# STM32.net
KiCad netlist of a schematic drawn in Altium Designer
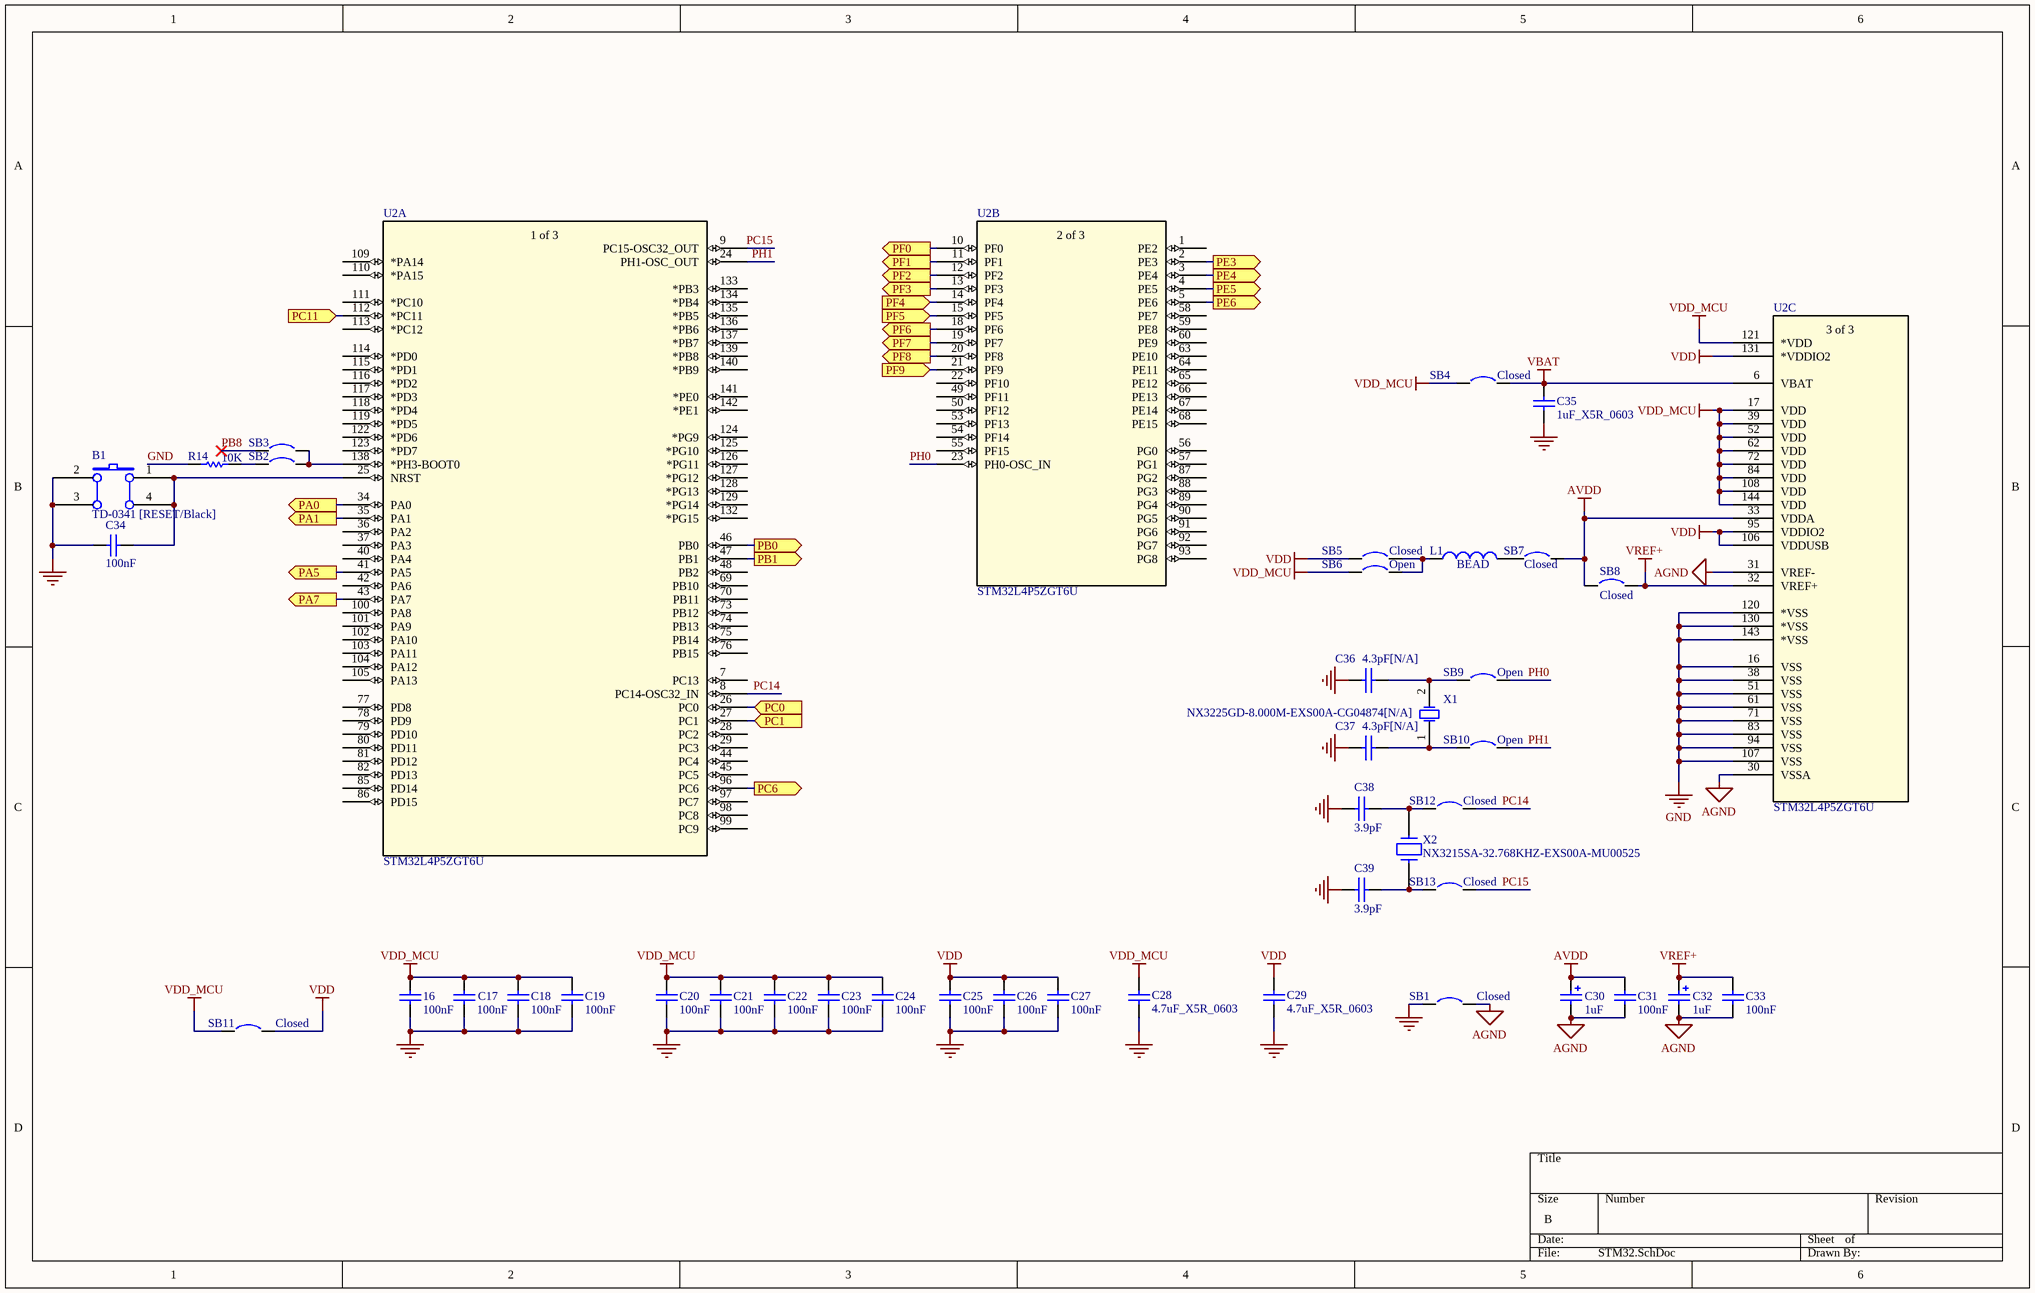
[diagram p0: STM32.SchDoc]

(export (version "E")
  (design (tool "Eeschema 10.0.6"))
  (components
    (comp (ref "16")
      (value "100nF")
      (footprint "0603C")
      (description "Capacitor")
      (fields (field (name "PUBLISHER") "Altium Limited"))
      (libsource (lib "Miscellaneous Devices") (part "Cap"))
    )
    (comp (ref "B1")
      (value "TD-0341 [RESET/Black]")
      (footprint "PB-6X6mm-Black")
      (description "SE PUSHBUTTON")
      (libsource (lib "Documents") (part "SW PUSHBUTTON"))
    )
    (comp (ref "C17")
      (value "100nF")
      (footprint "0603C")
      (description "Capacitor")
      (fields (field (name "PUBLISHER") "Altium Limited"))
      (libsource (lib "Miscellaneous Devices") (part "Cap"))
    )
    (comp (ref "C18")
      (value "100nF")
      (footprint "0603C")
      (description "Capacitor")
      (fields (field (name "PUBLISHER") "Altium Limited"))
      (libsource (lib "Miscellaneous Devices") (part "Cap"))
    )
    (comp (ref "C19")
      (value "100nF")
      (footprint "0603C")
      (description "Capacitor")
      (fields (field (name "PUBLISHER") "Altium Limited"))
      (libsource (lib "Miscellaneous Devices") (part "Cap"))
    )
    (comp (ref "C20")
      (value "100nF")
      (footprint "0603C")
      (description "Capacitor")
      (fields (field (name "PUBLISHER") "Altium Limited"))
      (libsource (lib "Miscellaneous Devices") (part "Cap"))
    )
    (comp (ref "C21")
      (value "100nF")
      (footprint "0603C")
      (description "Capacitor")
      (fields (field (name "PUBLISHER") "Altium Limited"))
      (libsource (lib "Miscellaneous Devices") (part "Cap"))
    )
    (comp (ref "C22")
      (value "100nF")
      (footprint "0603C")
      (description "Capacitor")
      (fields (field (name "PUBLISHER") "Altium Limited"))
      (libsource (lib "Miscellaneous Devices") (part "Cap"))
    )
    (comp (ref "C23")
      (value "100nF")
      (footprint "0603C")
      (description "Capacitor")
      (fields (field (name "PUBLISHER") "Altium Limited"))
      (libsource (lib "Miscellaneous Devices") (part "Cap"))
    )
    (comp (ref "C24")
      (value "100nF")
      (footprint "0603C")
      (description "Capacitor")
      (fields (field (name "PUBLISHER") "Altium Limited"))
      (libsource (lib "Miscellaneous Devices") (part "Cap"))
    )
    (comp (ref "C25")
      (value "100nF")
      (footprint "0603C")
      (description "Capacitor")
      (fields (field (name "PUBLISHER") "Altium Limited"))
      (libsource (lib "Miscellaneous Devices") (part "Cap"))
    )
    (comp (ref "C26")
      (value "100nF")
      (footprint "0603C")
      (description "Capacitor")
      (fields (field (name "PUBLISHER") "Altium Limited"))
      (libsource (lib "Miscellaneous Devices") (part "Cap"))
    )
    (comp (ref "C27")
      (value "100nF")
      (footprint "0603C")
      (description "Capacitor")
      (fields (field (name "PUBLISHER") "Altium Limited"))
      (libsource (lib "Miscellaneous Devices") (part "Cap"))
    )
    (comp (ref "C28")
      (value "4.7uF_X5R_0603")
      (footprint "0603C")
      (description "0603  X5R 4.7uF")
      (fields (field (name "TOLERANCE") "10%"))
      (libsource (lib "MB963_1") (part "CAP SMD 0603  X5R 1µF 25V 10%"))
    )
    (comp (ref "C29")
      (value "4.7uF_X5R_0603")
      (footprint "0603C")
      (description "0603  X5R 4.7uF")
      (fields (field (name "TOLERANCE") "10%"))
      (libsource (lib "MB963_1") (part "CAP SMD 0603  X5R 1µF 25V 10%"))
    )
    (comp (ref "C30")
      (value "1uF")
      (footprint "TAN-A")
      (description "Tan Capacitor,1uF,10%,16V,Tan-A,TAJA105K016R")
      (fields (field (name "Comment") "TAJA105K016R") (field (name "PUBLISHER") "Altium Limited"))
      (libsource (lib "Miscellaneous Devices") (part "Cap Pol1"))
    )
    (comp (ref "C31")
      (value "100nF")
      (footprint "0603C")
      (description "Capacitor")
      (fields (field (name "PUBLISHER") "Altium Limited"))
      (libsource (lib "Miscellaneous Devices") (part "Cap"))
    )
    (comp (ref "C32")
      (value "1uF")
      (footprint "TAN-A")
      (description "Tan Capacitor,1uF,10%,16V,Tan-A,TAJA105K016R")
      (fields (field (name "Comment") "TAJA105K016R") (field (name "PUBLISHER") "Altium Limited"))
      (libsource (lib "Miscellaneous Devices") (part "Cap Pol1"))
    )
    (comp (ref "C33")
      (value "100nF")
      (footprint "0603C")
      (description "Capacitor")
      (fields (field (name "PUBLISHER") "Altium Limited"))
      (libsource (lib "Miscellaneous Devices") (part "Cap"))
    )
    (comp (ref "C34")
      (value "100nF")
      (footprint "0603C")
      (description "Capacitor")
      (fields (field (name "PUBLISHER") "Altium Limited"))
      (libsource (lib "Miscellaneous Devices") (part "CAP"))
    )
    (comp (ref "C35")
      (value "1uF_X5R_0603")
      (footprint "0603C")
      (description "0603  X5R 1µF")
      (fields (field (name "TOLERANCE") "10%"))
      (libsource (lib "MB963_1") (part "CAP SMD 0603  X5R 1µF 25V 10%"))
    )
    (comp (ref "C36")
      (value "4.3pF[N/A]")
      (footprint "0603C")
      (description "Capacitor")
      (libsource (lib "*") (part "CAP"))
    )
    (comp (ref "C37")
      (value "4.3pF[N/A]")
      (footprint "0603C")
      (description "Capacitor")
      (libsource (lib "*") (part "CAP"))
    )
    (comp (ref "C38")
      (value "3.9pF")
      (footprint "0603C")
      (description "Capacitor")
      (libsource (lib "") (part "CAP_1"))
    )
    (comp (ref "C39")
      (value "3.9pF")
      (footprint "0603C")
      (description "Capacitor")
      (libsource (lib "") (part "CAP_1"))
    )
    (comp (ref "L1")
      (value "BEAD")
      (footprint "0603L")
      (description "Inductor")
      (fields (field (name "PUBLISHER") "Altium Limited"))
      (libsource (lib "Miscellaneous Devices") (part "Inductor"))
    )
    (comp (ref "R14")
      (value "10K")
      (footprint "0603R")
      (description "Resistor")
      (fields (field (name "PUBLISHER") "Altium Limited"))
      (libsource (lib "Miscellaneous Devices") (part "res1"))
    )
    (comp (ref "SB1")
      (value "Closed")
      (footprint "SB_0603")
      (description "Circuit Breaker")
      (fields (field (name "PUBLISHER") "Altium Limited"))
      (libsource (lib "MB1167") (part "Circuit Breaker_close"))
    )
    (comp (ref "SB2")
      (value "Circuit Breaker")
      (footprint "SB_0603")
      (fields (field (name "PUBLISHER") "Altium Limited"))
      (libsource (lib "MCD_TOOLS") (part "Circuit Breaker"))
    )
    (comp (ref "SB3")
      (value "Circuit Breaker")
      (footprint "SB_0603")
      (fields (field (name "PUBLISHER") "Altium Limited"))
      (libsource (lib "MCD_TOOLS") (part "Circuit Breaker"))
    )
    (comp (ref "SB4")
      (value "Closed")
      (footprint "SB_0603")
      (description "Circuit Breaker")
      (fields (field (name "PUBLISHER") "Altium Limited"))
      (libsource (lib "MB1167") (part "Circuit Breaker_close"))
    )
    (comp (ref "SB5")
      (value "Closed")
      (footprint "SB_0603")
      (description "Circuit Breaker")
      (fields (field (name "PUBLISHER") "Altium Limited"))
      (libsource (lib "MB1167") (part "Circuit Breaker_close"))
    )
    (comp (ref "SB6")
      (value "Open")
      (footprint "SB_0603")
      (description "Circuit Breaker")
      (fields (field (name "PUBLISHER") "Altium Limited"))
      (libsource (lib "MB1167") (part "Circuit Breaker"))
    )
    (comp (ref "SB7")
      (value "Closed")
      (footprint "SB_0603")
      (description "Circuit Breaker")
      (fields (field (name "PUBLISHER") "Altium Limited"))
      (libsource (lib "MB1167") (part "Circuit Breaker_close"))
    )
    (comp (ref "SB8")
      (value "Closed")
      (footprint "SB_0603")
      (description "Circuit Breaker")
      (fields (field (name "PUBLISHER") "Altium Limited"))
      (libsource (lib "MB1167") (part "Circuit Breaker_close"))
    )
    (comp (ref "SB9")
      (value "Open")
      (footprint "SB_0603")
      (description "Circuit Breaker")
      (fields (field (name "PUBLISHER") "Altium Limited"))
      (libsource (lib "MB1167") (part "Circuit Breaker"))
    )
    (comp (ref "SB10")
      (value "Open")
      (footprint "SB_0603")
      (description "Circuit Breaker")
      (fields (field (name "PUBLISHER") "Altium Limited"))
      (libsource (lib "MB1167") (part "Circuit Breaker"))
    )
    (comp (ref "SB11")
      (value "Closed")
      (footprint "SB_0603")
      (description "Circuit Breaker")
      (fields (field (name "PUBLISHER") "Altium Limited"))
      (libsource (lib "MB1167") (part "Circuit Breaker_close"))
    )
    (comp (ref "SB12")
      (value "Closed")
      (footprint "SB_0603")
      (description "Circuit Breaker")
      (fields (field (name "PUBLISHER") "Altium Limited"))
      (libsource (lib "MB1167") (part "Circuit Breaker"))
    )
    (comp (ref "SB13")
      (value "Closed")
      (footprint "SB_0603")
      (description "Circuit Breaker")
      (fields (field (name "PUBLISHER") "Altium Limited"))
      (libsource (lib "MB1167") (part "Circuit Breaker"))
    )
    (comp (ref "U2")
      (value "STM32L4P5ZGT6U")
      (footprint "LQFP144_STM32_STM")
      (description "No Description Available")
      (fields (field (name "COPYRIGHT") "Copyright (C) 2022 Ultra Librarian. All rights reserved."))
      (libsource (lib "STM32L4P5ZGT6U") (part "STM32L4P5ZGT6U"))
    )
    (comp (ref "X1")
      (value "NX3225GD-8.000M-EXS00A-CG04874[N/A]")
      (footprint "OSC_2SM_3R2x2R5")
      (description "Crystal Oscillator")
      (fields (field (name "PUBLISHER") "Altium Limited"))
      (libsource (lib "MB963_1") (part "XTAL"))
    )
    (comp (ref "X2")
      (value "NX3215SA-32.768KHZ-EXS00A-MU00525")
      (footprint "XTAL_2SM_3R2X1R5")
      (description "Crystal")
      (libsource (lib "MB1167") (part "CRYSTAL_32K"))
    )
  )
  (nets
    (net (code "1") (name "/PA0") (class "Default")
      (node (ref "U2") (pin "34") (pinfunction "PA0_34") (pintype "bidirectional"))
    )
    (net (code "2") (name "/PA1") (class "Default")
      (node (ref "U2") (pin "35") (pinfunction "PA1_35") (pintype "bidirectional"))
    )
    (net (code "3") (name "/PA5") (class "Default")
      (node (ref "U2") (pin "41") (pinfunction "PA5_41") (pintype "bidirectional"))
    )
    (net (code "4") (name "/PA7") (class "Default")
      (node (ref "U2") (pin "43") (pinfunction "PA7_43") (pintype "bidirectional"))
    )
    (net (code "5") (name "/PB0") (class "Default")
      (node (ref "U2") (pin "46") (pinfunction "PB0_46") (pintype "bidirectional"))
    )
    (net (code "6") (name "/PB1") (class "Default")
      (node (ref "U2") (pin "47") (pinfunction "PB1_47") (pintype "bidirectional"))
    )
    (net (code "7") (name "/PB8") (class "Default")
      (node (ref "SB3") (pin "1") (pinfunction "1_1") (pintype "passive+no_connect"))
    )
    (net (code "8") (name "/PC0") (class "Default")
      (node (ref "U2") (pin "26") (pinfunction "PC0_26") (pintype "bidirectional"))
    )
    (net (code "9") (name "/PC1") (class "Default")
      (node (ref "U2") (pin "27") (pinfunction "PC1_27") (pintype "bidirectional"))
    )
    (net (code "10") (name "/PC6") (class "Default")
      (node (ref "U2") (pin "96") (pinfunction "PC6_96") (pintype "bidirectional"))
    )
    (net (code "11") (name "/PC11") (class "Default")
      (node (ref "U2") (pin "112") (pinfunction "*PC11_112") (pintype "bidirectional"))
    )
    (net (code "12") (name "/PC14") (class "Default")
      (node (ref "SB12") (pin "2") (pinfunction "2_2") (pintype "passive"))
      (node (ref "U2") (pin "8") (pinfunction "PC14-OSC32_IN_8") (pintype "bidirectional"))
    )
    (net (code "13") (name "/PC15") (class "Default")
      (node (ref "SB13") (pin "2") (pinfunction "2_2") (pintype "passive"))
      (node (ref "U2") (pin "9") (pinfunction "PC15-OSC32_OUT_9") (pintype "bidirectional"))
    )
    (net (code "14") (name "/PE3") (class "Default")
      (node (ref "U2") (pin "2") (pinfunction "PE3_2") (pintype "bidirectional"))
    )
    (net (code "15") (name "/PE4") (class "Default")
      (node (ref "U2") (pin "3") (pinfunction "PE4_3") (pintype "bidirectional"))
    )
    (net (code "16") (name "/PE5") (class "Default")
      (node (ref "U2") (pin "4") (pinfunction "PE5_4") (pintype "bidirectional"))
    )
    (net (code "17") (name "/PE6") (class "Default")
      (node (ref "U2") (pin "5") (pinfunction "PE6_5") (pintype "bidirectional"))
    )
    (net (code "18") (name "/PF0") (class "Default")
      (node (ref "U2") (pin "10") (pinfunction "PF0_10") (pintype "bidirectional"))
    )
    (net (code "19") (name "/PF1") (class "Default")
      (node (ref "U2") (pin "11") (pinfunction "PF1_11") (pintype "bidirectional"))
    )
    (net (code "20") (name "/PF2") (class "Default")
      (node (ref "U2") (pin "12") (pinfunction "PF2_12") (pintype "bidirectional"))
    )
    (net (code "21") (name "/PF3") (class "Default")
      (node (ref "U2") (pin "13") (pinfunction "PF3_13") (pintype "bidirectional"))
    )
    (net (code "22") (name "/PF4") (class "Default")
      (node (ref "U2") (pin "14") (pinfunction "PF4_14") (pintype "bidirectional"))
    )
    (net (code "23") (name "/PF5") (class "Default")
      (node (ref "U2") (pin "15") (pinfunction "PF5_15") (pintype "bidirectional"))
    )
    (net (code "24") (name "/PF6") (class "Default")
      (node (ref "U2") (pin "18") (pinfunction "PF6_18") (pintype "bidirectional"))
    )
    (net (code "25") (name "/PF7") (class "Default")
      (node (ref "U2") (pin "19") (pinfunction "PF7_19") (pintype "bidirectional"))
    )
    (net (code "26") (name "/PF8") (class "Default")
      (node (ref "U2") (pin "20") (pinfunction "PF8_20") (pintype "bidirectional"))
    )
    (net (code "27") (name "/PF9") (class "Default")
      (node (ref "U2") (pin "21") (pinfunction "PF9_21") (pintype "bidirectional"))
    )
    (net (code "28") (name "/PH0") (class "Default")
      (node (ref "SB9") (pin "2") (pinfunction "2_2") (pintype "passive"))
      (node (ref "U2") (pin "23") (pinfunction "PH0-OSC_IN_23") (pintype "bidirectional"))
    )
    (net (code "29") (name "/PH1") (class "Default")
      (node (ref "SB10") (pin "2") (pinfunction "2_2") (pintype "passive"))
      (node (ref "U2") (pin "24") (pinfunction "PH1-OSC_OUT_24") (pintype "bidirectional"))
    )
    (net (code "30") (name "AGND") (class "Default")
      (node (ref "C30") (pin "2") (pinfunction "2_2") (pintype "passive"))
      (node (ref "C31") (pin "2") (pinfunction "2_2") (pintype "passive"))
      (node (ref "C32") (pin "2") (pinfunction "2_2") (pintype "passive"))
      (node (ref "C33") (pin "2") (pinfunction "2_2") (pintype "passive"))
      (node (ref "SB1") (pin "2") (pinfunction "2_2") (pintype "passive"))
      (node (ref "U2") (pin "30") (pinfunction "VSSA_30") (pintype "passive"))
      (node (ref "U2") (pin "31") (pinfunction "VREF-_31") (pintype "power_in"))
    )
    (net (code "31") (name "AVDD") (class "Default")
      (node (ref "C30") (pin "1") (pinfunction "1_1") (pintype "passive"))
      (node (ref "C31") (pin "1") (pinfunction "1_1") (pintype "passive"))
      (node (ref "SB7") (pin "2") (pinfunction "2_2") (pintype "passive"))
      (node (ref "SB8") (pin "1") (pinfunction "1_1") (pintype "passive"))
      (node (ref "U2") (pin "33") (pinfunction "VDDA_33") (pintype "power_in"))
    )
    (net (code "32") (name "GND") (class "Default")
      (node (ref "16") (pin "2") (pinfunction "2_2") (pintype "passive"))
      (node (ref "B1") (pin "2") (pinfunction "B0_2") (pintype "passive"))
      (node (ref "B1") (pin "3") (pinfunction "B1_3") (pintype "passive"))
      (node (ref "C17") (pin "2") (pinfunction "2_2") (pintype "passive"))
      (node (ref "C18") (pin "2") (pinfunction "2_2") (pintype "passive"))
      (node (ref "C19") (pin "2") (pinfunction "2_2") (pintype "passive"))
      (node (ref "C20") (pin "2") (pinfunction "2_2") (pintype "passive"))
      (node (ref "C21") (pin "2") (pinfunction "2_2") (pintype "passive"))
      (node (ref "C22") (pin "2") (pinfunction "2_2") (pintype "passive"))
      (node (ref "C23") (pin "2") (pinfunction "2_2") (pintype "passive"))
      (node (ref "C24") (pin "2") (pinfunction "2_2") (pintype "passive"))
      (node (ref "C25") (pin "2") (pinfunction "2_2") (pintype "passive"))
      (node (ref "C26") (pin "2") (pinfunction "2_2") (pintype "passive"))
      (node (ref "C27") (pin "2") (pinfunction "2_2") (pintype "passive"))
      (node (ref "C28") (pin "2") (pinfunction "2_2") (pintype "passive"))
      (node (ref "C29") (pin "2") (pinfunction "2_2") (pintype "passive"))
      (node (ref "C34") (pin "2") (pinfunction "2_2") (pintype "passive"))
      (node (ref "C35") (pin "2") (pinfunction "2_2") (pintype "passive"))
      (node (ref "C36") (pin "2") (pinfunction "2_2") (pintype "passive"))
      (node (ref "C37") (pin "2") (pinfunction "2_2") (pintype "passive"))
      (node (ref "C38") (pin "2") (pinfunction "2_2") (pintype "passive"))
      (node (ref "C39") (pin "2") (pinfunction "2_2") (pintype "passive"))
      (node (ref "R14") (pin "2") (pinfunction "2_2") (pintype "passive"))
      (node (ref "SB1") (pin "1") (pinfunction "1_1") (pintype "passive"))
      (node (ref "U2") (pin "107") (pinfunction "VSS_107") (pintype "passive"))
      (node (ref "U2") (pin "120") (pinfunction "*VSS_120") (pintype "passive"))
      (node (ref "U2") (pin "130") (pinfunction "*VSS_130") (pintype "passive"))
      (node (ref "U2") (pin "143") (pinfunction "*VSS_143") (pintype "passive"))
      (node (ref "U2") (pin "16") (pinfunction "VSS_16") (pintype "passive"))
      (node (ref "U2") (pin "38") (pinfunction "VSS_38") (pintype "passive"))
      (node (ref "U2") (pin "51") (pinfunction "VSS_51") (pintype "passive"))
      (node (ref "U2") (pin "61") (pinfunction "VSS_61") (pintype "passive"))
      (node (ref "U2") (pin "71") (pinfunction "VSS_71") (pintype "passive"))
      (node (ref "U2") (pin "83") (pinfunction "VSS_83") (pintype "passive"))
      (node (ref "U2") (pin "94") (pinfunction "VSS_94") (pintype "passive"))
    )
    (net (code "33") (name "Net-(B1-A0)") (class "Default")
      (node (ref "B1") (pin "1") (pinfunction "A0_1") (pintype "passive"))
      (node (ref "B1") (pin "4") (pinfunction "A1_4") (pintype "passive"))
      (node (ref "C34") (pin "1") (pinfunction "1_1") (pintype "passive"))
      (node (ref "U2") (pin "25") (pinfunction "NRST_25") (pintype "bidirectional"))
    )
    (net (code "34") (name "Net-(C38-Pad1)") (class "Default")
      (node (ref "C38") (pin "1") (pinfunction "1_1") (pintype "passive"))
      (node (ref "SB12") (pin "1") (pinfunction "1_1") (pintype "passive"))
      (node (ref "X2") (pin "1") (pinfunction "1_1") (pintype "passive"))
    )
    (net (code "35") (name "Net-(C39-Pad1)") (class "Default")
      (node (ref "C39") (pin "1") (pinfunction "1_1") (pintype "passive"))
      (node (ref "SB13") (pin "1") (pinfunction "1_1") (pintype "passive"))
      (node (ref "X2") (pin "2") (pinfunction "2_2") (pintype "passive"))
    )
    (net (code "36") (name "Net-(L1-Pad1)") (class "Default")
      (node (ref "L1") (pin "1") (pinfunction "1_1") (pintype "passive"))
      (node (ref "SB5") (pin "2") (pinfunction "2_2") (pintype "passive"))
      (node (ref "SB6") (pin "2") (pinfunction "2_2") (pintype "passive"))
    )
    (net (code "37") (name "Net-(L1-Pad2)") (class "Default")
      (node (ref "L1") (pin "2") (pinfunction "2_2") (pintype "passive"))
      (node (ref "SB7") (pin "1") (pinfunction "1_1") (pintype "passive"))
    )
    (net (code "38") (name "Net-(R14-Pad1)") (class "Default")
      (node (ref "R14") (pin "1") (pinfunction "1_1") (pintype "passive"))
      (node (ref "SB2") (pin "1") (pinfunction "1_1") (pintype "passive"))
    )
    (net (code "39") (name "Net-(U2A-*PH3-BOOT0)") (class "Default")
      (node (ref "SB2") (pin "2") (pinfunction "2_2") (pintype "passive"))
      (node (ref "SB3") (pin "2") (pinfunction "2_2") (pintype "passive"))
      (node (ref "U2") (pin "138") (pinfunction "*PH3-BOOT0_138") (pintype "bidirectional"))
    )
    (net (code "40") (name "Net-(X1-OSC1)") (class "Default")
      (node (ref "C37") (pin "1") (pinfunction "1_1") (pintype "passive"))
      (node (ref "SB10") (pin "1") (pinfunction "1_1") (pintype "passive"))
      (node (ref "X1") (pin "1") (pinfunction "OSC1_1") (pintype "passive"))
    )
    (net (code "41") (name "Net-(X1-OSC2)") (class "Default")
      (node (ref "C36") (pin "1") (pinfunction "1_1") (pintype "passive"))
      (node (ref "SB9") (pin "1") (pinfunction "1_1") (pintype "passive"))
      (node (ref "X1") (pin "2") (pinfunction "OSC2_2") (pintype "passive"))
    )
    (net (code "42") (name "VBAT") (class "Default")
      (node (ref "C35") (pin "1") (pinfunction "1_1") (pintype "passive"))
      (node (ref "SB4") (pin "2") (pinfunction "2_2") (pintype "passive"))
      (node (ref "U2") (pin "6") (pinfunction "VBAT_6") (pintype "power_in"))
    )
    (net (code "43") (name "VDD") (class "Default")
      (node (ref "C25") (pin "1") (pinfunction "1_1") (pintype "passive"))
      (node (ref "C26") (pin "1") (pinfunction "1_1") (pintype "passive"))
      (node (ref "C27") (pin "1") (pinfunction "1_1") (pintype "passive"))
      (node (ref "C29") (pin "1") (pinfunction "1_1") (pintype "passive"))
      (node (ref "SB11") (pin "2") (pinfunction "2_2") (pintype "passive"))
      (node (ref "SB5") (pin "1") (pinfunction "1_1") (pintype "passive"))
      (node (ref "U2") (pin "106") (pinfunction "VDDUSB_106") (pintype "power_in"))
      (node (ref "U2") (pin "131") (pinfunction "*VDDIO2_131") (pintype "power_in"))
      (node (ref "U2") (pin "95") (pinfunction "VDDIO2_95") (pintype "power_in"))
    )
    (net (code "44") (name "VDD_MCU") (class "Default")
      (node (ref "16") (pin "1") (pinfunction "1_1") (pintype "passive"))
      (node (ref "C17") (pin "1") (pinfunction "1_1") (pintype "passive"))
      (node (ref "C18") (pin "1") (pinfunction "1_1") (pintype "passive"))
      (node (ref "C19") (pin "1") (pinfunction "1_1") (pintype "passive"))
      (node (ref "C20") (pin "1") (pinfunction "1_1") (pintype "passive"))
      (node (ref "C21") (pin "1") (pinfunction "1_1") (pintype "passive"))
      (node (ref "C22") (pin "1") (pinfunction "1_1") (pintype "passive"))
      (node (ref "C23") (pin "1") (pinfunction "1_1") (pintype "passive"))
      (node (ref "C24") (pin "1") (pinfunction "1_1") (pintype "passive"))
      (node (ref "C28") (pin "1") (pinfunction "1_1") (pintype "passive"))
      (node (ref "SB11") (pin "1") (pinfunction "1_1") (pintype "passive"))
      (node (ref "SB4") (pin "1") (pinfunction "1_1") (pintype "passive"))
      (node (ref "SB6") (pin "1") (pinfunction "1_1") (pintype "passive"))
      (node (ref "U2") (pin "108") (pinfunction "VDD_108") (pintype "power_in"))
      (node (ref "U2") (pin "121") (pinfunction "*VDD_121") (pintype "power_in"))
      (node (ref "U2") (pin "144") (pinfunction "VDD_144") (pintype "power_in"))
      (node (ref "U2") (pin "17") (pinfunction "VDD_17") (pintype "power_in"))
      (node (ref "U2") (pin "39") (pinfunction "VDD_39") (pintype "power_in"))
      (node (ref "U2") (pin "52") (pinfunction "VDD_52") (pintype "power_in"))
      (node (ref "U2") (pin "62") (pinfunction "VDD_62") (pintype "power_in"))
      (node (ref "U2") (pin "72") (pinfunction "VDD_72") (pintype "power_in"))
      (node (ref "U2") (pin "84") (pinfunction "VDD_84") (pintype "power_in"))
    )
    (net (code "45") (name "VREF+") (class "Default")
      (node (ref "C32") (pin "1") (pinfunction "1_1") (pintype "passive"))
      (node (ref "C33") (pin "1") (pinfunction "1_1") (pintype "passive"))
      (node (ref "SB8") (pin "2") (pinfunction "2_2") (pintype "passive"))
      (node (ref "U2") (pin "32") (pinfunction "VREF+_32") (pintype "power_in"))
    )
    (net (code "46") (name "unconnected-(U2A-*PA14-Pad109)") (class "Default")
      (node (ref "U2") (pin "109") (pinfunction "*PA14_109") (pintype "bidirectional"))
    )
    (net (code "47") (name "unconnected-(U2A-*PA15-Pad110)") (class "Default")
      (node (ref "U2") (pin "110") (pinfunction "*PA15_110") (pintype "bidirectional"))
    )
    (net (code "48") (name "unconnected-(U2A-*PB3-Pad133)") (class "Default")
      (node (ref "U2") (pin "133") (pinfunction "*PB3_133") (pintype "bidirectional"))
    )
    (net (code "49") (name "unconnected-(U2A-*PB4-Pad134)") (class "Default")
      (node (ref "U2") (pin "134") (pinfunction "*PB4_134") (pintype "bidirectional"))
    )
    (net (code "50") (name "unconnected-(U2A-*PB5-Pad135)") (class "Default")
      (node (ref "U2") (pin "135") (pinfunction "*PB5_135") (pintype "bidirectional"))
    )
    (net (code "51") (name "unconnected-(U2A-*PB6-Pad136)") (class "Default")
      (node (ref "U2") (pin "136") (pinfunction "*PB6_136") (pintype "bidirectional"))
    )
    (net (code "52") (name "unconnected-(U2A-*PB7-Pad137)") (class "Default")
      (node (ref "U2") (pin "137") (pinfunction "*PB7_137") (pintype "bidirectional"))
    )
    (net (code "53") (name "unconnected-(U2A-*PB8-Pad139)") (class "Default")
      (node (ref "U2") (pin "139") (pinfunction "*PB8_139") (pintype "bidirectional"))
    )
    (net (code "54") (name "unconnected-(U2A-*PB9-Pad140)") (class "Default")
      (node (ref "U2") (pin "140") (pinfunction "*PB9_140") (pintype "bidirectional"))
    )
    (net (code "55") (name "unconnected-(U2A-*PC10-Pad111)") (class "Default")
      (node (ref "U2") (pin "111") (pinfunction "*PC10_111") (pintype "bidirectional"))
    )
    (net (code "56") (name "unconnected-(U2A-*PC12-Pad113)") (class "Default")
      (node (ref "U2") (pin "113") (pinfunction "*PC12_113") (pintype "bidirectional"))
    )
    (net (code "57") (name "unconnected-(U2A-*PD0-Pad114)") (class "Default")
      (node (ref "U2") (pin "114") (pinfunction "*PD0_114") (pintype "bidirectional"))
    )
    (net (code "58") (name "unconnected-(U2A-*PD1-Pad115)") (class "Default")
      (node (ref "U2") (pin "115") (pinfunction "*PD1_115") (pintype "bidirectional"))
    )
    (net (code "59") (name "unconnected-(U2A-*PD2-Pad116)") (class "Default")
      (node (ref "U2") (pin "116") (pinfunction "*PD2_116") (pintype "bidirectional"))
    )
    (net (code "60") (name "unconnected-(U2A-*PD3-Pad117)") (class "Default")
      (node (ref "U2") (pin "117") (pinfunction "*PD3_117") (pintype "bidirectional"))
    )
    (net (code "61") (name "unconnected-(U2A-*PD4-Pad118)") (class "Default")
      (node (ref "U2") (pin "118") (pinfunction "*PD4_118") (pintype "bidirectional"))
    )
    (net (code "62") (name "unconnected-(U2A-*PD5-Pad119)") (class "Default")
      (node (ref "U2") (pin "119") (pinfunction "*PD5_119") (pintype "bidirectional"))
    )
    (net (code "63") (name "unconnected-(U2A-*PD6-Pad122)") (class "Default")
      (node (ref "U2") (pin "122") (pinfunction "*PD6_122") (pintype "bidirectional"))
    )
    (net (code "64") (name "unconnected-(U2A-*PD7-Pad123)") (class "Default")
      (node (ref "U2") (pin "123") (pinfunction "*PD7_123") (pintype "bidirectional"))
    )
    (net (code "65") (name "unconnected-(U2A-*PE0-Pad141)") (class "Default")
      (node (ref "U2") (pin "141") (pinfunction "*PE0_141") (pintype "bidirectional"))
    )
    (net (code "66") (name "unconnected-(U2A-*PE1-Pad142)") (class "Default")
      (node (ref "U2") (pin "142") (pinfunction "*PE1_142") (pintype "bidirectional"))
    )
    (net (code "67") (name "unconnected-(U2A-*PG9-Pad124)") (class "Default")
      (node (ref "U2") (pin "124") (pinfunction "*PG9_124") (pintype "bidirectional"))
    )
    (net (code "68") (name "unconnected-(U2A-*PG10-Pad125)") (class "Default")
      (node (ref "U2") (pin "125") (pinfunction "*PG10_125") (pintype "bidirectional"))
    )
    (net (code "69") (name "unconnected-(U2A-*PG11-Pad126)") (class "Default")
      (node (ref "U2") (pin "126") (pinfunction "*PG11_126") (pintype "bidirectional"))
    )
    (net (code "70") (name "unconnected-(U2A-*PG12-Pad127)") (class "Default")
      (node (ref "U2") (pin "127") (pinfunction "*PG12_127") (pintype "bidirectional"))
    )
    (net (code "71") (name "unconnected-(U2A-*PG13-Pad128)") (class "Default")
      (node (ref "U2") (pin "128") (pinfunction "*PG13_128") (pintype "bidirectional"))
    )
    (net (code "72") (name "unconnected-(U2A-*PG14-Pad129)") (class "Default")
      (node (ref "U2") (pin "129") (pinfunction "*PG14_129") (pintype "bidirectional"))
    )
    (net (code "73") (name "unconnected-(U2A-*PG15-Pad132)") (class "Default")
      (node (ref "U2") (pin "132") (pinfunction "*PG15_132") (pintype "bidirectional"))
    )
    (net (code "74") (name "unconnected-(U2A-PA2-Pad36)") (class "Default")
      (node (ref "U2") (pin "36") (pinfunction "PA2_36") (pintype "bidirectional"))
    )
    (net (code "75") (name "unconnected-(U2A-PA3-Pad37)") (class "Default")
      (node (ref "U2") (pin "37") (pinfunction "PA3_37") (pintype "bidirectional"))
    )
    (net (code "76") (name "unconnected-(U2A-PA4-Pad40)") (class "Default")
      (node (ref "U2") (pin "40") (pinfunction "PA4_40") (pintype "bidirectional"))
    )
    (net (code "77") (name "unconnected-(U2A-PA6-Pad42)") (class "Default")
      (node (ref "U2") (pin "42") (pinfunction "PA6_42") (pintype "bidirectional"))
    )
    (net (code "78") (name "unconnected-(U2A-PA8-Pad100)") (class "Default")
      (node (ref "U2") (pin "100") (pinfunction "PA8_100") (pintype "bidirectional"))
    )
    (net (code "79") (name "unconnected-(U2A-PA9-Pad101)") (class "Default")
      (node (ref "U2") (pin "101") (pinfunction "PA9_101") (pintype "bidirectional"))
    )
    (net (code "80") (name "unconnected-(U2A-PA10-Pad102)") (class "Default")
      (node (ref "U2") (pin "102") (pinfunction "PA10_102") (pintype "bidirectional"))
    )
    (net (code "81") (name "unconnected-(U2A-PA11-Pad103)") (class "Default")
      (node (ref "U2") (pin "103") (pinfunction "PA11_103") (pintype "bidirectional"))
    )
    (net (code "82") (name "unconnected-(U2A-PA12-Pad104)") (class "Default")
      (node (ref "U2") (pin "104") (pinfunction "PA12_104") (pintype "bidirectional"))
    )
    (net (code "83") (name "unconnected-(U2A-PA13-Pad105)") (class "Default")
      (node (ref "U2") (pin "105") (pinfunction "PA13_105") (pintype "bidirectional"))
    )
    (net (code "84") (name "unconnected-(U2A-PB2-Pad48)") (class "Default")
      (node (ref "U2") (pin "48") (pinfunction "PB2_48") (pintype "bidirectional"))
    )
    (net (code "85") (name "unconnected-(U2A-PB10-Pad69)") (class "Default")
      (node (ref "U2") (pin "69") (pinfunction "PB10_69") (pintype "bidirectional"))
    )
    (net (code "86") (name "unconnected-(U2A-PB11-Pad70)") (class "Default")
      (node (ref "U2") (pin "70") (pinfunction "PB11_70") (pintype "bidirectional"))
    )
    (net (code "87") (name "unconnected-(U2A-PB12-Pad73)") (class "Default")
      (node (ref "U2") (pin "73") (pinfunction "PB12_73") (pintype "bidirectional"))
    )
    (net (code "88") (name "unconnected-(U2A-PB13-Pad74)") (class "Default")
      (node (ref "U2") (pin "74") (pinfunction "PB13_74") (pintype "bidirectional"))
    )
    (net (code "89") (name "unconnected-(U2A-PB14-Pad75)") (class "Default")
      (node (ref "U2") (pin "75") (pinfunction "PB14_75") (pintype "bidirectional"))
    )
    (net (code "90") (name "unconnected-(U2A-PB15-Pad76)") (class "Default")
      (node (ref "U2") (pin "76") (pinfunction "PB15_76") (pintype "bidirectional"))
    )
    (net (code "91") (name "unconnected-(U2A-PC2-Pad28)") (class "Default")
      (node (ref "U2") (pin "28") (pinfunction "PC2_28") (pintype "bidirectional"))
    )
    (net (code "92") (name "unconnected-(U2A-PC3-Pad29)") (class "Default")
      (node (ref "U2") (pin "29") (pinfunction "PC3_29") (pintype "bidirectional"))
    )
    (net (code "93") (name "unconnected-(U2A-PC4-Pad44)") (class "Default")
      (node (ref "U2") (pin "44") (pinfunction "PC4_44") (pintype "bidirectional"))
    )
    (net (code "94") (name "unconnected-(U2A-PC5-Pad45)") (class "Default")
      (node (ref "U2") (pin "45") (pinfunction "PC5_45") (pintype "bidirectional"))
    )
    (net (code "95") (name "unconnected-(U2A-PC7-Pad97)") (class "Default")
      (node (ref "U2") (pin "97") (pinfunction "PC7_97") (pintype "bidirectional"))
    )
    (net (code "96") (name "unconnected-(U2A-PC8-Pad98)") (class "Default")
      (node (ref "U2") (pin "98") (pinfunction "PC8_98") (pintype "bidirectional"))
    )
    (net (code "97") (name "unconnected-(U2A-PC9-Pad99)") (class "Default")
      (node (ref "U2") (pin "99") (pinfunction "PC9_99") (pintype "bidirectional"))
    )
    (net (code "98") (name "unconnected-(U2A-PC13-Pad7)") (class "Default")
      (node (ref "U2") (pin "7") (pinfunction "PC13_7") (pintype "bidirectional"))
    )
    (net (code "99") (name "unconnected-(U2A-PD8-Pad77)") (class "Default")
      (node (ref "U2") (pin "77") (pinfunction "PD8_77") (pintype "bidirectional"))
    )
    (net (code "100") (name "unconnected-(U2A-PD9-Pad78)") (class "Default")
      (node (ref "U2") (pin "78") (pinfunction "PD9_78") (pintype "bidirectional"))
    )
    (net (code "101") (name "unconnected-(U2A-PD10-Pad79)") (class "Default")
      (node (ref "U2") (pin "79") (pinfunction "PD10_79") (pintype "bidirectional"))
    )
    (net (code "102") (name "unconnected-(U2A-PD11-Pad80)") (class "Default")
      (node (ref "U2") (pin "80") (pinfunction "PD11_80") (pintype "bidirectional"))
    )
    (net (code "103") (name "unconnected-(U2A-PD12-Pad81)") (class "Default")
      (node (ref "U2") (pin "81") (pinfunction "PD12_81") (pintype "bidirectional"))
    )
    (net (code "104") (name "unconnected-(U2A-PD13-Pad82)") (class "Default")
      (node (ref "U2") (pin "82") (pinfunction "PD13_82") (pintype "bidirectional"))
    )
    (net (code "105") (name "unconnected-(U2A-PD14-Pad85)") (class "Default")
      (node (ref "U2") (pin "85") (pinfunction "PD14_85") (pintype "bidirectional"))
    )
    (net (code "106") (name "unconnected-(U2A-PD15-Pad86)") (class "Default")
      (node (ref "U2") (pin "86") (pinfunction "PD15_86") (pintype "bidirectional"))
    )
    (net (code "107") (name "unconnected-(U2B-PE2-Pad1)") (class "Default")
      (node (ref "U2") (pin "1") (pinfunction "PE2_1") (pintype "bidirectional"))
    )
    (net (code "108") (name "unconnected-(U2B-PE7-Pad58)") (class "Default")
      (node (ref "U2") (pin "58") (pinfunction "PE7_58") (pintype "bidirectional"))
    )
    (net (code "109") (name "unconnected-(U2B-PE8-Pad59)") (class "Default")
      (node (ref "U2") (pin "59") (pinfunction "PE8_59") (pintype "bidirectional"))
    )
    (net (code "110") (name "unconnected-(U2B-PE9-Pad60)") (class "Default")
      (node (ref "U2") (pin "60") (pinfunction "PE9_60") (pintype "bidirectional"))
    )
    (net (code "111") (name "unconnected-(U2B-PE10-Pad63)") (class "Default")
      (node (ref "U2") (pin "63") (pinfunction "PE10_63") (pintype "bidirectional"))
    )
    (net (code "112") (name "unconnected-(U2B-PE11-Pad64)") (class "Default")
      (node (ref "U2") (pin "64") (pinfunction "PE11_64") (pintype "bidirectional"))
    )
    (net (code "113") (name "unconnected-(U2B-PE12-Pad65)") (class "Default")
      (node (ref "U2") (pin "65") (pinfunction "PE12_65") (pintype "bidirectional"))
    )
    (net (code "114") (name "unconnected-(U2B-PE13-Pad66)") (class "Default")
      (node (ref "U2") (pin "66") (pinfunction "PE13_66") (pintype "bidirectional"))
    )
    (net (code "115") (name "unconnected-(U2B-PE14-Pad67)") (class "Default")
      (node (ref "U2") (pin "67") (pinfunction "PE14_67") (pintype "bidirectional"))
    )
    (net (code "116") (name "unconnected-(U2B-PE15-Pad68)") (class "Default")
      (node (ref "U2") (pin "68") (pinfunction "PE15_68") (pintype "bidirectional"))
    )
    (net (code "117") (name "unconnected-(U2B-PF10-Pad22)") (class "Default")
      (node (ref "U2") (pin "22") (pinfunction "PF10_22") (pintype "bidirectional"))
    )
    (net (code "118") (name "unconnected-(U2B-PF11-Pad49)") (class "Default")
      (node (ref "U2") (pin "49") (pinfunction "PF11_49") (pintype "bidirectional"))
    )
    (net (code "119") (name "unconnected-(U2B-PF12-Pad50)") (class "Default")
      (node (ref "U2") (pin "50") (pinfunction "PF12_50") (pintype "bidirectional"))
    )
    (net (code "120") (name "unconnected-(U2B-PF13-Pad53)") (class "Default")
      (node (ref "U2") (pin "53") (pinfunction "PF13_53") (pintype "bidirectional"))
    )
    (net (code "121") (name "unconnected-(U2B-PF14-Pad54)") (class "Default")
      (node (ref "U2") (pin "54") (pinfunction "PF14_54") (pintype "bidirectional"))
    )
    (net (code "122") (name "unconnected-(U2B-PF15-Pad55)") (class "Default")
      (node (ref "U2") (pin "55") (pinfunction "PF15_55") (pintype "bidirectional"))
    )
    (net (code "123") (name "unconnected-(U2B-PG0-Pad56)") (class "Default")
      (node (ref "U2") (pin "56") (pinfunction "PG0_56") (pintype "bidirectional"))
    )
    (net (code "124") (name "unconnected-(U2B-PG1-Pad57)") (class "Default")
      (node (ref "U2") (pin "57") (pinfunction "PG1_57") (pintype "bidirectional"))
    )
    (net (code "125") (name "unconnected-(U2B-PG2-Pad87)") (class "Default")
      (node (ref "U2") (pin "87") (pinfunction "PG2_87") (pintype "bidirectional"))
    )
    (net (code "126") (name "unconnected-(U2B-PG3-Pad88)") (class "Default")
      (node (ref "U2") (pin "88") (pinfunction "PG3_88") (pintype "bidirectional"))
    )
    (net (code "127") (name "unconnected-(U2B-PG4-Pad89)") (class "Default")
      (node (ref "U2") (pin "89") (pinfunction "PG4_89") (pintype "bidirectional"))
    )
    (net (code "128") (name "unconnected-(U2B-PG5-Pad90)") (class "Default")
      (node (ref "U2") (pin "90") (pinfunction "PG5_90") (pintype "bidirectional"))
    )
    (net (code "129") (name "unconnected-(U2B-PG6-Pad91)") (class "Default")
      (node (ref "U2") (pin "91") (pinfunction "PG6_91") (pintype "bidirectional"))
    )
    (net (code "130") (name "unconnected-(U2B-PG7-Pad92)") (class "Default")
      (node (ref "U2") (pin "92") (pinfunction "PG7_92") (pintype "bidirectional"))
    )
    (net (code "131") (name "unconnected-(U2B-PG8-Pad93)") (class "Default")
      (node (ref "U2") (pin "93") (pinfunction "PG8_93") (pintype "bidirectional"))
    )
  )
)
